# Indikator.net
KiCad netlist of a schematic drawn in Altium Designer
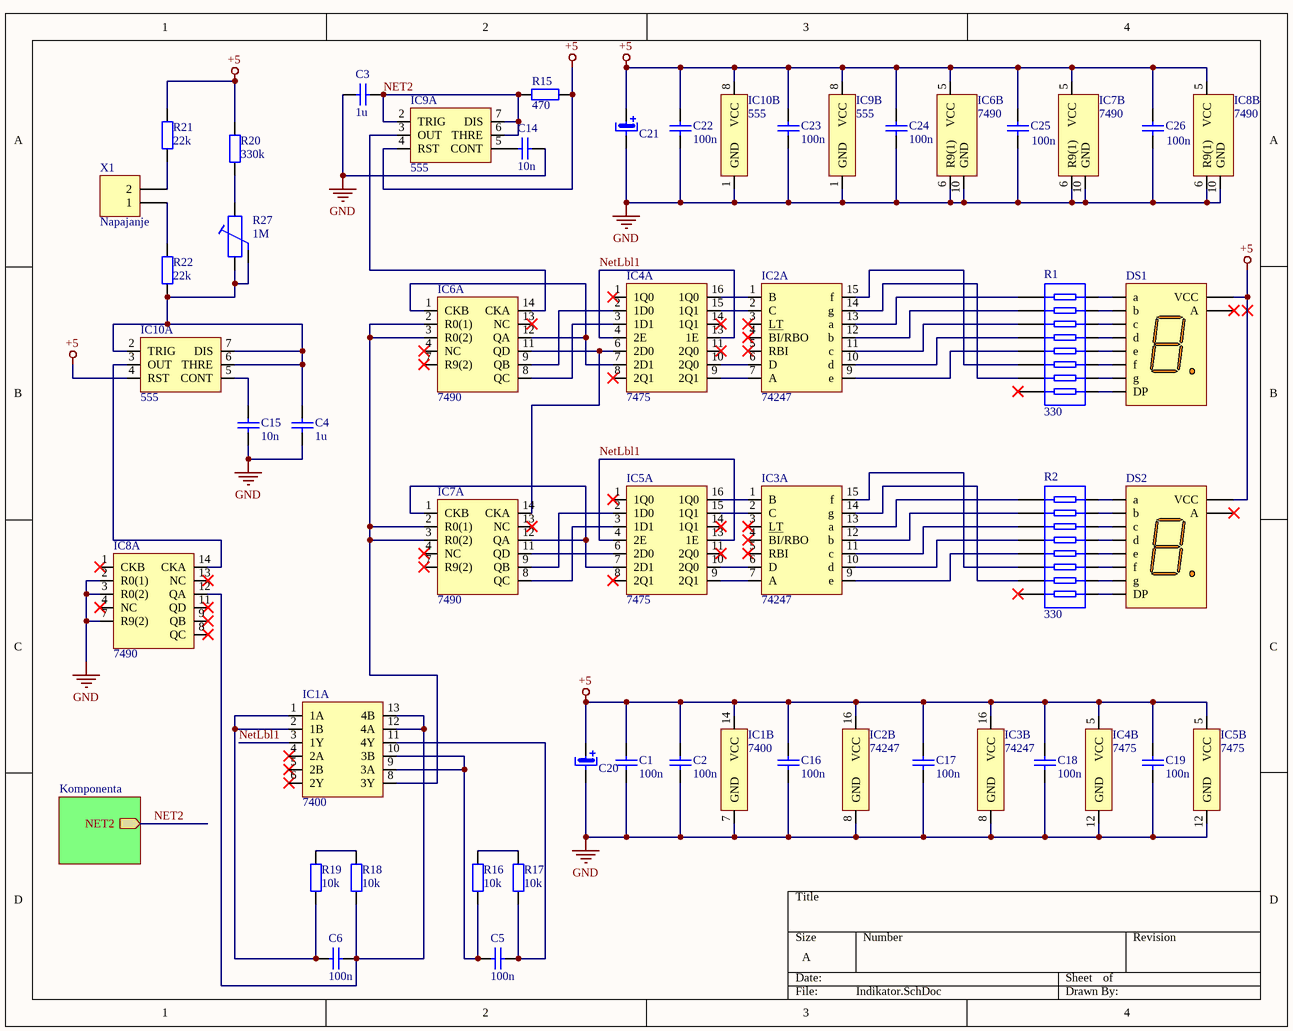
[diagram p0: Indikator.SchDoc]

(export (version "E")
  (design (tool "Eeschema 10.0.6"))
  (components
    (comp (ref "C1")
      (value "100n")
      (footprint "RAD-0.3")
      (description "Capacitor")
      (fields (field (name "PUBLISHER") "Altium Limited"))
      (libsource (lib "Miscellaneous Devices") (part "Cap"))
    )
    (comp (ref "C2")
      (value "100n")
      (footprint "RAD-0.3")
      (description "Capacitor")
      (fields (field (name "PUBLISHER") "Altium Limited"))
      (libsource (lib "Miscellaneous Devices") (part "Cap"))
    )
    (comp (ref "C3")
      (value "1u")
      (footprint "RAD-0.3")
      (description "Capacitor")
      (fields (field (name "PUBLISHER") "Altium Limited"))
      (libsource (lib "Miscellaneous Devices") (part "Cap"))
    )
    (comp (ref "C4")
      (value "1u")
      (footprint "RAD-0.3")
      (description "Capacitor")
      (fields (field (name "PUBLISHER") "Altium Limited"))
      (libsource (lib "Miscellaneous Devices") (part "Cap"))
    )
    (comp (ref "C5")
      (value "100n")
      (footprint "RAD-0.3")
      (description "Capacitor")
      (fields (field (name "PUBLISHER") "Altium Limited"))
      (libsource (lib "Miscellaneous Devices") (part "Cap"))
    )
    (comp (ref "C6")
      (value "100n")
      (footprint "RAD-0.3")
      (description "Capacitor")
      (fields (field (name "PUBLISHER") "Altium Limited"))
      (libsource (lib "Miscellaneous Devices") (part "Cap"))
    )
    (comp (ref "C14")
      (value "10n")
      (footprint "RAD-0.3")
      (description "Capacitor")
      (fields (field (name "PUBLISHER") "Altium Limited"))
      (libsource (lib "Miscellaneous Devices") (part "Cap"))
    )
    (comp (ref "C15")
      (value "10n")
      (footprint "RAD-0.3")
      (description "Capacitor")
      (fields (field (name "PUBLISHER") "Altium Limited"))
      (libsource (lib "Miscellaneous Devices") (part "Cap"))
    )
    (comp (ref "C16")
      (value "100n")
      (footprint "RAD-0.3")
      (description "Capacitor")
      (fields (field (name "PUBLISHER") "Altium Limited"))
      (libsource (lib "Miscellaneous Devices") (part "Cap"))
    )
    (comp (ref "C17")
      (value "100n")
      (footprint "RAD-0.3")
      (description "Capacitor")
      (fields (field (name "PUBLISHER") "Altium Limited"))
      (libsource (lib "Miscellaneous Devices") (part "Cap"))
    )
    (comp (ref "C18")
      (value "100n")
      (footprint "RAD-0.3")
      (description "Capacitor")
      (fields (field (name "PUBLISHER") "Altium Limited"))
      (libsource (lib "Miscellaneous Devices") (part "Cap"))
    )
    (comp (ref "C19")
      (value "100n")
      (footprint "RAD-0.3")
      (description "Capacitor")
      (fields (field (name "PUBLISHER") "Altium Limited"))
      (libsource (lib "Miscellaneous Devices") (part "Cap"))
    )
    (comp (ref "C20") (value "Elko") (footprint "RB7.6-15") (libsource (lib "Indikator_lib") (part "Elko")))
    (comp (ref "C21") (value "Elko") (footprint "RB7.6-15") (libsource (lib "Indikator_lib") (part "Elko")))
    (comp (ref "C22")
      (value "100n")
      (footprint "RAD-0.3")
      (description "Capacitor")
      (fields (field (name "PUBLISHER") "Altium Limited"))
      (libsource (lib "Miscellaneous Devices") (part "Cap"))
    )
    (comp (ref "C23")
      (value "100n")
      (footprint "RAD-0.3")
      (description "Capacitor")
      (fields (field (name "PUBLISHER") "Altium Limited"))
      (libsource (lib "Miscellaneous Devices") (part "Cap"))
    )
    (comp (ref "C24")
      (value "100n")
      (footprint "RAD-0.3")
      (description "Capacitor")
      (fields (field (name "PUBLISHER") "Altium Limited"))
      (libsource (lib "Miscellaneous Devices") (part "Cap"))
    )
    (comp (ref "C25")
      (value "100n")
      (footprint "RAD-0.3")
      (description "Capacitor")
      (fields (field (name "PUBLISHER") "Altium Limited"))
      (libsource (lib "Miscellaneous Devices") (part "Cap"))
    )
    (comp (ref "C26")
      (value "100n")
      (footprint "RAD-0.3")
      (description "Capacitor")
      (fields (field (name "PUBLISHER") "Altium Limited"))
      (libsource (lib "Miscellaneous Devices") (part "Cap"))
    )
    (comp (ref "DS1")
      (value "Dpy Amber-CA")
      (footprint "A")
      (description "7.62 mm Black Surface Orange 7-Segment Display: CA, RH DP")
      (fields (field (name "PUBLISHER") "Altium Limited"))
      (libsource (lib "Miscellaneous Devices") (part "Dpy Amber-CA"))
    )
    (comp (ref "DS2")
      (value "Dpy Amber-CA")
      (footprint "A")
      (description "7.62 mm Black Surface Orange 7-Segment Display: CA, RH DP")
      (fields (field (name "PUBLISHER") "Altium Limited"))
      (libsource (lib "Miscellaneous Devices") (part "Dpy Amber-CA"))
    )
    (comp (ref "IC1") (value "7400") (footprint "DIP-14") (libsource (lib "Indikator_lib") (part "7400")))
    (comp (ref "IC2") (value "74247") (footprint "DIP-16") (libsource (lib "Indikator_lib") (part "74247")))
    (comp (ref "IC3") (value "74247") (footprint "DIP-16") (libsource (lib "Indikator_lib") (part "74247")))
    (comp (ref "IC4") (value "7475") (footprint "DIP-16") (libsource (lib "Indikator_lib") (part "7475")))
    (comp (ref "IC5") (value "7475") (footprint "DIP-16") (libsource (lib "Indikator_lib") (part "7475")))
    (comp (ref "IC6") (value "7490") (footprint "DIP-14") (libsource (lib "Indikator_lib") (part "7490")))
    (comp (ref "IC7") (value "7490") (footprint "DIP-14") (libsource (lib "Indikator_lib") (part "7490")))
    (comp (ref "IC8") (value "7490") (footprint "DIP-14") (libsource (lib "Indikator_lib") (part "7490")))
    (comp (ref "IC9") (value "555") (footprint "DIP-8") (libsource (lib "Indikator_lib") (part "555")))
    (comp (ref "IC10") (value "555") (footprint "DIP-8") (libsource (lib "Indikator_lib") (part "555")))
    (comp (ref "R1")
      (value "330")
      (footprint "SSOP16_N")
      (description "Isolated Resistor Network")
      (fields (field (name "PUBLISHER") "Altium Limited"))
      (libsource (lib "Miscellaneous Devices") (part "Res Pack4"))
    )
    (comp (ref "R2")
      (value "330")
      (footprint "SSOP16_N")
      (description "Isolated Resistor Network")
      (fields (field (name "PUBLISHER") "Altium Limited"))
      (libsource (lib "Miscellaneous Devices") (part "Res Pack4"))
    )
    (comp (ref "R15")
      (value "470")
      (footprint "AXIAL-0.4")
      (description "Resistor")
      (fields (field (name "PUBLISHER") "Altium Limited"))
      (libsource (lib "") (part "Res2_2"))
    )
    (comp (ref "R16")
      (value "10k")
      (footprint "AXIAL-0.4")
      (description "Resistor")
      (fields (field (name "PUBLISHER") "Altium Limited"))
      (libsource (lib "") (part "Res2_1"))
    )
    (comp (ref "R17")
      (value "10k")
      (footprint "AXIAL-0.4")
      (description "Resistor")
      (fields (field (name "PUBLISHER") "Altium Limited"))
      (libsource (lib "") (part "Res2_1"))
    )
    (comp (ref "R18")
      (value "10k")
      (footprint "AXIAL-0.4")
      (description "Resistor")
      (fields (field (name "PUBLISHER") "Altium Limited"))
      (libsource (lib "") (part "Res2_1"))
    )
    (comp (ref "R19")
      (value "10k")
      (footprint "AXIAL-0.4")
      (description "Resistor")
      (fields (field (name "PUBLISHER") "Altium Limited"))
      (libsource (lib "") (part "Res2_1"))
    )
    (comp (ref "R20")
      (value "330k")
      (footprint "AXIAL-0.4")
      (description "Resistor")
      (fields (field (name "PUBLISHER") "Altium Limited"))
      (libsource (lib "") (part "Res2_1"))
    )
    (comp (ref "R21")
      (value "22k")
      (footprint "AXIAL-0.4")
      (description "Resistor")
      (fields (field (name "PUBLISHER") "Altium Limited"))
      (libsource (lib "") (part "Res2_1"))
    )
    (comp (ref "R22")
      (value "22k")
      (footprint "AXIAL-0.4")
      (description "Resistor")
      (fields (field (name "PUBLISHER") "Altium Limited"))
      (libsource (lib "Miscellaneous Devices") (part "Res2"))
    )
    (comp (ref "R27") (value "1M") (footprint "14-1210") (libsource (lib "Indikator_lib") (part "Trimmer")))
    (comp (ref "X1")
      (value "Napajanje")
      (footprint "HDR1X2")
      (description "Header, 2-Pin")
      (fields (field (name "PUBLISHER") "Altium Limited"))
      (libsource (lib "Miscellaneous Connectors") (part "Header 2"))
    )
  )
  (nets
    (net (code "1") (name "+5") (class "Default")
      (node (ref "C1") (pin "2") (pinfunction "2_2") (pintype "passive"))
      (node (ref "C16") (pin "2") (pinfunction "2_2") (pintype "passive"))
      (node (ref "C17") (pin "2") (pinfunction "2_2") (pintype "passive"))
      (node (ref "C18") (pin "2") (pinfunction "2_2") (pintype "passive"))
      (node (ref "C19") (pin "2") (pinfunction "2_2") (pintype "passive"))
      (node (ref "C2") (pin "2") (pinfunction "2_2") (pintype "passive"))
      (node (ref "C20") (pin "1") (pinfunction "16_1") (pintype "passive"))
      (node (ref "C21") (pin "1") (pinfunction "16_1") (pintype "passive"))
      (node (ref "C22") (pin "2") (pinfunction "2_2") (pintype "passive"))
      (node (ref "C23") (pin "2") (pinfunction "2_2") (pintype "passive"))
      (node (ref "C24") (pin "2") (pinfunction "2_2") (pintype "passive"))
      (node (ref "C25") (pin "2") (pinfunction "2_2") (pintype "passive"))
      (node (ref "C26") (pin "2") (pinfunction "2_2") (pintype "passive"))
      (node (ref "DS1") (pin "1") (pinfunction "VCC_1") (pintype "passive"))
      (node (ref "DS2") (pin "1") (pinfunction "VCC_1") (pintype "passive"))
      (node (ref "IC1") (pin "14") (pinfunction "VCC_14") (pintype "passive"))
      (node (ref "IC10") (pin "4") (pinfunction "RST_4") (pintype "passive"))
      (node (ref "IC10") (pin "8") (pinfunction "VCC_8") (pintype "passive"))
      (node (ref "IC2") (pin "16") (pinfunction "VCC_16") (pintype "passive"))
      (node (ref "IC3") (pin "16") (pinfunction "VCC_16") (pintype "passive"))
      (node (ref "IC4") (pin "5") (pinfunction "VCC_5") (pintype "passive"))
      (node (ref "IC5") (pin "5") (pinfunction "VCC_5") (pintype "passive"))
      (node (ref "IC6") (pin "5") (pinfunction "VCC_5") (pintype "passive"))
      (node (ref "IC7") (pin "5") (pinfunction "VCC_5") (pintype "passive"))
      (node (ref "IC8") (pin "5") (pinfunction "VCC_5") (pintype "passive"))
      (node (ref "IC9") (pin "4") (pinfunction "RST_4") (pintype "passive"))
      (node (ref "IC9") (pin "8") (pinfunction "VCC_8") (pintype "passive"))
      (node (ref "R15") (pin "2") (pinfunction "2_2") (pintype "passive"))
      (node (ref "R20") (pin "2") (pinfunction "2_2") (pintype "passive"))
      (node (ref "R21") (pin "2") (pinfunction "2_2") (pintype "passive"))
    )
    (net (code "2") (name "/NET2") (class "Default")
      (node (ref "C3") (pin "2") (pinfunction "2_2") (pintype "passive"))
      (node (ref "IC9") (pin "2") (pinfunction "TRIG_2") (pintype "passive"))
      (node (ref "IC9") (pin "6") (pinfunction "THRE_6") (pintype "passive"))
      (node (ref "IC9") (pin "7") (pinfunction "DIS_7") (pintype "passive"))
      (node (ref "R15") (pin "1") (pinfunction "1_1") (pintype "passive"))
    )
    (net (code "3") (name "/NetLbl1") (class "Default")
      (node (ref "IC1") (pin "3") (pinfunction "1Y_3") (pintype "passive"))
      (node (ref "IC4") (pin "13") (pinfunction "1E_13") (pintype "passive"))
      (node (ref "IC4") (pin "4") (pinfunction "2E_4") (pintype "passive"))
      (node (ref "IC5") (pin "13") (pinfunction "1E_13") (pintype "passive"))
      (node (ref "IC5") (pin "4") (pinfunction "2E_4") (pintype "passive"))
    )
    (net (code "4") (name "GND") (class "Default")
      (node (ref "C1") (pin "1") (pinfunction "1_1") (pintype "passive"))
      (node (ref "C14") (pin "2") (pinfunction "2_2") (pintype "passive"))
      (node (ref "C15") (pin "1") (pinfunction "1_1") (pintype "passive"))
      (node (ref "C16") (pin "1") (pinfunction "1_1") (pintype "passive"))
      (node (ref "C17") (pin "1") (pinfunction "1_1") (pintype "passive"))
      (node (ref "C18") (pin "1") (pinfunction "1_1") (pintype "passive"))
      (node (ref "C19") (pin "1") (pinfunction "1_1") (pintype "passive"))
      (node (ref "C2") (pin "1") (pinfunction "1_1") (pintype "passive"))
      (node (ref "C20") (pin "2") (pintype "passive"))
      (node (ref "C21") (pin "2") (pintype "passive"))
      (node (ref "C22") (pin "1") (pinfunction "1_1") (pintype "passive"))
      (node (ref "C23") (pin "1") (pinfunction "1_1") (pintype "passive"))
      (node (ref "C24") (pin "1") (pinfunction "1_1") (pintype "passive"))
      (node (ref "C25") (pin "1") (pinfunction "1_1") (pintype "passive"))
      (node (ref "C26") (pin "1") (pinfunction "1_1") (pintype "passive"))
      (node (ref "C3") (pin "1") (pinfunction "1_1") (pintype "passive"))
      (node (ref "C4") (pin "2") (pinfunction "2_2") (pintype "passive"))
      (node (ref "IC1") (pin "7") (pinfunction "GND_7") (pintype "passive"))
      (node (ref "IC10") (pin "1") (pinfunction "GND_1") (pintype "passive"))
      (node (ref "IC2") (pin "8") (pinfunction "GND_8") (pintype "passive"))
      (node (ref "IC3") (pin "8") (pinfunction "GND_8") (pintype "passive"))
      (node (ref "IC4") (pin "12") (pinfunction "GND_12") (pintype "passive"))
      (node (ref "IC5") (pin "12") (pinfunction "GND_12") (pintype "passive"))
      (node (ref "IC6") (pin "10") (pinfunction "GND_10") (pintype "passive"))
      (node (ref "IC6") (pin "6") (pinfunction "R9(1)_6") (pintype "passive"))
      (node (ref "IC7") (pin "10") (pinfunction "GND_10") (pintype "passive"))
      (node (ref "IC7") (pin "6") (pinfunction "R9(1)_6") (pintype "passive"))
      (node (ref "IC8") (pin "10") (pinfunction "GND_10") (pintype "passive"))
      (node (ref "IC8") (pin "2") (pinfunction "R0(1)_2") (pintype "passive"))
      (node (ref "IC8") (pin "3") (pinfunction "R0(2)_3") (pintype "passive"))
      (node (ref "IC8") (pin "6") (pinfunction "R9(1)_6") (pintype "passive"))
      (node (ref "IC8") (pin "7") (pinfunction "R9(2)_7") (pintype "passive"))
      (node (ref "IC9") (pin "1") (pinfunction "GND_1") (pintype "passive"))
    )
    (net (code "5") (name "Net-(DS1-DP)") (class "Default")
      (node (ref "DS1") (pin "7") (pinfunction "DP_7") (pintype "passive"))
      (node (ref "R1") (pin "9") (pinfunction "9_9") (pintype "passive"))
    )
    (net (code "6") (name "Net-(DS1-a)") (class "Default")
      (node (ref "DS1") (pin "10") (pinfunction "a_10") (pintype "passive"))
      (node (ref "R1") (pin "16") (pinfunction "16_16") (pintype "passive"))
    )
    (net (code "7") (name "Net-(DS1-b)") (class "Default")
      (node (ref "DS1") (pin "9") (pinfunction "b_9") (pintype "passive"))
      (node (ref "R1") (pin "15") (pinfunction "15_15") (pintype "passive"))
    )
    (net (code "8") (name "Net-(DS1-c)") (class "Default")
      (node (ref "DS1") (pin "8") (pinfunction "c_8") (pintype "passive"))
      (node (ref "R1") (pin "14") (pinfunction "14_14") (pintype "passive"))
    )
    (net (code "9") (name "Net-(DS1-d)") (class "Default")
      (node (ref "DS1") (pin "5") (pinfunction "d_5") (pintype "passive"))
      (node (ref "R1") (pin "13") (pinfunction "13_13") (pintype "passive"))
    )
    (net (code "10") (name "Net-(DS1-e)") (class "Default")
      (node (ref "DS1") (pin "4") (pinfunction "e_4") (pintype "passive"))
      (node (ref "R1") (pin "12") (pinfunction "12_12") (pintype "passive"))
    )
    (net (code "11") (name "Net-(DS1-f)") (class "Default")
      (node (ref "DS1") (pin "2") (pinfunction "f_2") (pintype "passive"))
      (node (ref "R1") (pin "11") (pinfunction "11_11") (pintype "passive"))
    )
    (net (code "12") (name "Net-(DS1-g)") (class "Default")
      (node (ref "DS1") (pin "3") (pinfunction "g_3") (pintype "passive"))
      (node (ref "R1") (pin "10") (pinfunction "10_10") (pintype "passive"))
    )
    (net (code "13") (name "Net-(DS2-DP)") (class "Default")
      (node (ref "DS2") (pin "7") (pinfunction "DP_7") (pintype "passive"))
      (node (ref "R2") (pin "9") (pinfunction "9_9") (pintype "passive"))
    )
    (net (code "14") (name "Net-(DS2-a)") (class "Default")
      (node (ref "DS2") (pin "10") (pinfunction "a_10") (pintype "passive"))
      (node (ref "R2") (pin "16") (pinfunction "16_16") (pintype "passive"))
    )
    (net (code "15") (name "Net-(DS2-b)") (class "Default")
      (node (ref "DS2") (pin "9") (pinfunction "b_9") (pintype "passive"))
      (node (ref "R2") (pin "15") (pinfunction "15_15") (pintype "passive"))
    )
    (net (code "16") (name "Net-(DS2-c)") (class "Default")
      (node (ref "DS2") (pin "8") (pinfunction "c_8") (pintype "passive"))
      (node (ref "R2") (pin "14") (pinfunction "14_14") (pintype "passive"))
    )
    (net (code "17") (name "Net-(DS2-d)") (class "Default")
      (node (ref "DS2") (pin "5") (pinfunction "d_5") (pintype "passive"))
      (node (ref "R2") (pin "13") (pinfunction "13_13") (pintype "passive"))
    )
    (net (code "18") (name "Net-(DS2-e)") (class "Default")
      (node (ref "DS2") (pin "4") (pinfunction "e_4") (pintype "passive"))
      (node (ref "R2") (pin "12") (pinfunction "12_12") (pintype "passive"))
    )
    (net (code "19") (name "Net-(DS2-f)") (class "Default")
      (node (ref "DS2") (pin "2") (pinfunction "f_2") (pintype "passive"))
      (node (ref "R2") (pin "11") (pinfunction "11_11") (pintype "passive"))
    )
    (net (code "20") (name "Net-(DS2-g)") (class "Default")
      (node (ref "DS2") (pin "3") (pinfunction "g_3") (pintype "passive"))
      (node (ref "R2") (pin "10") (pinfunction "10_10") (pintype "passive"))
    )
    (net (code "21") (name "Net-(IC1A-1A)") (class "Default")
      (node (ref "C6") (pin "2") (pinfunction "2_2") (pintype "passive"))
      (node (ref "IC1") (pin "1") (pinfunction "1A_1") (pintype "passive"))
      (node (ref "IC1") (pin "2") (pinfunction "1B_2") (pintype "passive"))
      (node (ref "R19") (pin "1") (pinfunction "1_1") (pintype "passive"))
    )
    (net (code "22") (name "Net-(IC1A-3A)") (class "Default")
      (node (ref "C5") (pin "2") (pinfunction "2_2") (pintype "passive"))
      (node (ref "IC1") (pin "10") (pinfunction "3B_10") (pintype "passive"))
      (node (ref "IC1") (pin "9") (pinfunction "3A_9") (pintype "passive"))
      (node (ref "R16") (pin "1") (pinfunction "1_1") (pintype "passive"))
    )
    (net (code "23") (name "Net-(IC1A-3Y)") (class "Default")
      (node (ref "IC1") (pin "8") (pinfunction "3Y_8") (pintype "passive"))
      (node (ref "IC6") (pin "2") (pinfunction "R0(1)_2") (pintype "passive"))
      (node (ref "IC6") (pin "3") (pinfunction "R0(2)_3") (pintype "passive"))
      (node (ref "IC7") (pin "2") (pinfunction "R0(1)_2") (pintype "passive"))
      (node (ref "IC7") (pin "3") (pinfunction "R0(2)_3") (pintype "passive"))
    )
    (net (code "24") (name "Net-(IC1A-4A)") (class "Default")
      (node (ref "C6") (pin "1") (pinfunction "1_1") (pintype "passive"))
      (node (ref "IC1") (pin "12") (pinfunction "4A_12") (pintype "passive"))
      (node (ref "IC1") (pin "13") (pinfunction "4B_13") (pintype "passive"))
      (node (ref "IC8") (pin "12") (pinfunction "QA_12") (pintype "passive"))
      (node (ref "R18") (pin "1") (pinfunction "1_1") (pintype "passive"))
    )
    (net (code "25") (name "Net-(IC1A-4Y)") (class "Default")
      (node (ref "C5") (pin "1") (pinfunction "1_1") (pintype "passive"))
      (node (ref "IC1") (pin "11") (pinfunction "4Y_11") (pintype "passive"))
      (node (ref "R17") (pin "1") (pinfunction "1_1") (pintype "passive"))
    )
    (net (code "26") (name "Net-(IC2A-A)") (class "Default")
      (node (ref "IC2") (pin "7") (pinfunction "A_7") (pintype "passive"))
      (node (ref "IC4") (pin "9") (pinfunction "2Q1_9") (pintype "passive"))
    )
    (net (code "27") (name "Net-(IC2A-B)") (class "Default")
      (node (ref "IC2") (pin "1") (pinfunction "B_1") (pintype "passive"))
      (node (ref "IC4") (pin "16") (pinfunction "1Q0_16") (pintype "passive"))
    )
    (net (code "28") (name "Net-(IC2A-C)") (class "Default")
      (node (ref "IC2") (pin "2") (pinfunction "C_2") (pintype "passive"))
      (node (ref "IC4") (pin "15") (pinfunction "1Q1_15") (pintype "passive"))
    )
    (net (code "29") (name "Net-(IC2A-D)") (class "Default")
      (node (ref "IC2") (pin "6") (pinfunction "D_6") (pintype "passive"))
      (node (ref "IC4") (pin "10") (pinfunction "2Q0_10") (pintype "passive"))
    )
    (net (code "30") (name "Net-(IC2A-a)") (class "Default")
      (node (ref "IC2") (pin "13") (pinfunction "a_13") (pintype "passive"))
      (node (ref "R1") (pin "1") (pinfunction "1_1") (pintype "passive"))
    )
    (net (code "31") (name "Net-(IC2A-b)") (class "Default")
      (node (ref "IC2") (pin "12") (pinfunction "b_12") (pintype "passive"))
      (node (ref "R1") (pin "2") (pinfunction "2_2") (pintype "passive"))
    )
    (net (code "32") (name "Net-(IC2A-c)") (class "Default")
      (node (ref "IC2") (pin "11") (pinfunction "c_11") (pintype "passive"))
      (node (ref "R1") (pin "3") (pinfunction "3_3") (pintype "passive"))
    )
    (net (code "33") (name "Net-(IC2A-d)") (class "Default")
      (node (ref "IC2") (pin "10") (pinfunction "d_10") (pintype "passive"))
      (node (ref "R1") (pin "4") (pinfunction "4_4") (pintype "passive"))
    )
    (net (code "34") (name "Net-(IC2A-e)") (class "Default")
      (node (ref "IC2") (pin "9") (pinfunction "e_9") (pintype "passive"))
      (node (ref "R1") (pin "5") (pinfunction "5_5") (pintype "passive"))
    )
    (net (code "35") (name "Net-(IC2A-f)") (class "Default")
      (node (ref "IC2") (pin "15") (pinfunction "f_15") (pintype "passive"))
      (node (ref "R1") (pin "6") (pinfunction "6_6") (pintype "passive"))
    )
    (net (code "36") (name "Net-(IC2A-g)") (class "Default")
      (node (ref "IC2") (pin "14") (pinfunction "g_14") (pintype "passive"))
      (node (ref "R1") (pin "7") (pinfunction "7_7") (pintype "passive"))
    )
    (net (code "37") (name "Net-(IC3A-A)") (class "Default")
      (node (ref "IC3") (pin "7") (pinfunction "A_7") (pintype "passive"))
      (node (ref "IC5") (pin "9") (pinfunction "2Q1_9") (pintype "passive"))
    )
    (net (code "38") (name "Net-(IC3A-B)") (class "Default")
      (node (ref "IC3") (pin "1") (pinfunction "B_1") (pintype "passive"))
      (node (ref "IC5") (pin "16") (pinfunction "1Q0_16") (pintype "passive"))
    )
    (net (code "39") (name "Net-(IC3A-C)") (class "Default")
      (node (ref "IC3") (pin "2") (pinfunction "C_2") (pintype "passive"))
      (node (ref "IC5") (pin "15") (pinfunction "1Q1_15") (pintype "passive"))
    )
    (net (code "40") (name "Net-(IC3A-D)") (class "Default")
      (node (ref "IC3") (pin "6") (pinfunction "D_6") (pintype "passive"))
      (node (ref "IC5") (pin "10") (pinfunction "2Q0_10") (pintype "passive"))
    )
    (net (code "41") (name "Net-(IC3A-a)") (class "Default")
      (node (ref "IC3") (pin "13") (pinfunction "a_13") (pintype "passive"))
      (node (ref "R2") (pin "1") (pinfunction "1_1") (pintype "passive"))
    )
    (net (code "42") (name "Net-(IC3A-b)") (class "Default")
      (node (ref "IC3") (pin "12") (pinfunction "b_12") (pintype "passive"))
      (node (ref "R2") (pin "2") (pinfunction "2_2") (pintype "passive"))
    )
    (net (code "43") (name "Net-(IC3A-c)") (class "Default")
      (node (ref "IC3") (pin "11") (pinfunction "c_11") (pintype "passive"))
      (node (ref "R2") (pin "3") (pinfunction "3_3") (pintype "passive"))
    )
    (net (code "44") (name "Net-(IC3A-d)") (class "Default")
      (node (ref "IC3") (pin "10") (pinfunction "d_10") (pintype "passive"))
      (node (ref "R2") (pin "4") (pinfunction "4_4") (pintype "passive"))
    )
    (net (code "45") (name "Net-(IC3A-e)") (class "Default")
      (node (ref "IC3") (pin "9") (pinfunction "e_9") (pintype "passive"))
      (node (ref "R2") (pin "5") (pinfunction "5_5") (pintype "passive"))
    )
    (net (code "46") (name "Net-(IC3A-f)") (class "Default")
      (node (ref "IC3") (pin "15") (pinfunction "f_15") (pintype "passive"))
      (node (ref "R2") (pin "6") (pinfunction "6_6") (pintype "passive"))
    )
    (net (code "47") (name "Net-(IC3A-g)") (class "Default")
      (node (ref "IC3") (pin "14") (pinfunction "g_14") (pintype "passive"))
      (node (ref "R2") (pin "7") (pinfunction "7_7") (pintype "passive"))
    )
    (net (code "48") (name "Net-(IC4A-1D0)") (class "Default")
      (node (ref "IC4") (pin "2") (pinfunction "1D0_2") (pintype "passive"))
      (node (ref "IC6") (pin "9") (pinfunction "QB_9") (pintype "passive"))
    )
    (net (code "49") (name "Net-(IC4A-1D1)") (class "Default")
      (node (ref "IC4") (pin "3") (pinfunction "1D1_3") (pintype "passive"))
      (node (ref "IC6") (pin "8") (pinfunction "QC_8") (pintype "passive"))
    )
    (net (code "50") (name "Net-(IC4A-2D0)") (class "Default")
      (node (ref "IC4") (pin "6") (pinfunction "2D0_6") (pintype "passive"))
      (node (ref "IC6") (pin "11") (pinfunction "QD_11") (pintype "passive"))
      (node (ref "IC7") (pin "14") (pinfunction "CKA_14") (pintype "passive"))
    )
    (net (code "51") (name "Net-(IC4A-2D1)") (class "Default")
      (node (ref "IC4") (pin "7") (pinfunction "2D1_7") (pintype "passive"))
      (node (ref "IC6") (pin "1") (pinfunction "CKB_1") (pintype "passive"))
      (node (ref "IC6") (pin "12") (pinfunction "QA_12") (pintype "passive"))
    )
    (net (code "52") (name "Net-(IC5A-1D0)") (class "Default")
      (node (ref "IC5") (pin "2") (pinfunction "1D0_2") (pintype "passive"))
      (node (ref "IC7") (pin "9") (pinfunction "QB_9") (pintype "passive"))
    )
    (net (code "53") (name "Net-(IC5A-1D1)") (class "Default")
      (node (ref "IC5") (pin "3") (pinfunction "1D1_3") (pintype "passive"))
      (node (ref "IC7") (pin "8") (pinfunction "QC_8") (pintype "passive"))
    )
    (net (code "54") (name "Net-(IC5A-2D0)") (class "Default")
      (node (ref "IC5") (pin "6") (pinfunction "2D0_6") (pintype "passive"))
      (node (ref "IC7") (pin "11") (pinfunction "QD_11") (pintype "passive"))
    )
    (net (code "55") (name "Net-(IC5A-2D1)") (class "Default")
      (node (ref "IC5") (pin "7") (pinfunction "2D1_7") (pintype "passive"))
      (node (ref "IC7") (pin "1") (pinfunction "CKB_1") (pintype "passive"))
      (node (ref "IC7") (pin "12") (pinfunction "QA_12") (pintype "passive"))
    )
    (net (code "56") (name "Net-(IC6A-CKA)") (class "Default")
      (node (ref "IC6") (pin "14") (pinfunction "CKA_14") (pintype "passive"))
      (node (ref "IC9") (pin "3") (pinfunction "OUT_3") (pintype "passive"))
    )
    (net (code "57") (name "Net-(IC9A-CONT)") (class "Default")
      (node (ref "C14") (pin "1") (pinfunction "1_1") (pintype "passive"))
      (node (ref "IC9") (pin "5") (pinfunction "CONT_5") (pintype "passive"))
    )
    (net (code "58") (name "Net-(IC10A-CONT)") (class "Default")
      (node (ref "C15") (pin "2") (pinfunction "2_2") (pintype "passive"))
      (node (ref "IC10") (pin "5") (pinfunction "CONT_5") (pintype "passive"))
    )
    (net (code "59") (name "Net-(IC10A-DIS)") (class "Default")
      (node (ref "C4") (pin "1") (pinfunction "1_1") (pintype "passive"))
      (node (ref "IC10") (pin "2") (pinfunction "TRIG_2") (pintype "passive"))
      (node (ref "IC10") (pin "6") (pinfunction "THRE_6") (pintype "passive"))
      (node (ref "IC10") (pin "7") (pinfunction "DIS_7") (pintype "passive"))
      (node (ref "R22") (pin "2") (pinfunction "2_2") (pintype "passive"))
      (node (ref "R27") (pin "1") (pinfunction "1_1") (pintype "passive"))
      (node (ref "R27") (pin "2") (pinfunction "2_2") (pintype "passive"))
    )
    (net (code "60") (name "Net-(IC10A-OUT)") (class "Default")
      (node (ref "IC10") (pin "3") (pinfunction "OUT_3") (pintype "passive"))
      (node (ref "IC8") (pin "14") (pinfunction "CKA_14") (pintype "passive"))
    )
    (net (code "61") (name "Net-(R16-Pad2)") (class "Default")
      (node (ref "R16") (pin "2") (pinfunction "2_2") (pintype "passive"))
      (node (ref "R17") (pin "2") (pinfunction "2_2") (pintype "passive"))
    )
    (net (code "62") (name "Net-(R18-Pad2)") (class "Default")
      (node (ref "R18") (pin "2") (pinfunction "2_2") (pintype "passive"))
      (node (ref "R19") (pin "2") (pinfunction "2_2") (pintype "passive"))
    )
    (net (code "63") (name "Net-(R20-Pad1)") (class "Default")
      (node (ref "R20") (pin "1") (pinfunction "1_1") (pintype "passive"))
      (node (ref "R27") (pin "0") (pinfunction "0_0") (pintype "passive"))
    )
    (net (code "64") (name "Net-(R21-Pad1)") (class "Default")
      (node (ref "R21") (pin "1") (pinfunction "1_1") (pintype "passive"))
      (node (ref "X1") (pin "2") (pinfunction "2_2") (pintype "passive"))
    )
    (net (code "65") (name "Net-(R22-Pad1)") (class "Default")
      (node (ref "R22") (pin "1") (pinfunction "1_1") (pintype "passive"))
      (node (ref "X1") (pin "1") (pinfunction "1_1") (pintype "passive"))
    )
    (net (code "66") (name "unconnected-(DS1-A-Pad6)") (class "Default")
      (node (ref "DS1") (pin "6") (pinfunction "A_6") (pintype "passive+no_connect"))
    )
    (net (code "67") (name "unconnected-(DS2-A-Pad6)") (class "Default")
      (node (ref "DS2") (pin "6") (pinfunction "A_6") (pintype "passive+no_connect"))
    )
    (net (code "68") (name "unconnected-(IC1A-2A-Pad4)") (class "Default")
      (node (ref "IC1") (pin "4") (pinfunction "2A_4") (pintype "passive+no_connect"))
    )
    (net (code "69") (name "unconnected-(IC1A-2B-Pad5)") (class "Default")
      (node (ref "IC1") (pin "5") (pinfunction "2B_5") (pintype "passive+no_connect"))
    )
    (net (code "70") (name "unconnected-(IC1A-2Y-Pad6)") (class "Default")
      (node (ref "IC1") (pin "6") (pinfunction "2Y_6") (pintype "passive+no_connect"))
    )
    (net (code "71") (name "unconnected-(IC2A-BI{slash}RBO-Pad4)") (class "Default")
      (node (ref "IC2") (pin "4") (pinfunction "BI/RBO_4") (pintype "passive+no_connect"))
    )
    (net (code "72") (name "unconnected-(IC2A-LT-Pad3)") (class "Default")
      (node (ref "IC2") (pin "3") (pinfunction "LT_3") (pintype "passive+no_connect"))
    )
    (net (code "73") (name "unconnected-(IC2A-RBI-Pad5)") (class "Default")
      (node (ref "IC2") (pin "5") (pinfunction "RBI_5") (pintype "passive+no_connect"))
    )
    (net (code "74") (name "unconnected-(IC3A-BI{slash}RBO-Pad4)") (class "Default")
      (node (ref "IC3") (pin "4") (pinfunction "BI/RBO_4") (pintype "passive+no_connect"))
    )
    (net (code "75") (name "unconnected-(IC3A-LT-Pad3)") (class "Default")
      (node (ref "IC3") (pin "3") (pinfunction "LT_3") (pintype "passive+no_connect"))
    )
    (net (code "76") (name "unconnected-(IC3A-RBI-Pad5)") (class "Default")
      (node (ref "IC3") (pin "5") (pinfunction "RBI_5") (pintype "passive+no_connect"))
    )
    (net (code "77") (name "unconnected-(IC4A-1Q0-Pad1)") (class "Default")
      (node (ref "IC4") (pin "1") (pinfunction "1Q0_1") (pintype "passive+no_connect"))
    )
    (net (code "78") (name "unconnected-(IC4A-1Q1-Pad14)") (class "Default")
      (node (ref "IC4") (pin "14") (pinfunction "1Q1_14") (pintype "passive+no_connect"))
    )
    (net (code "79") (name "unconnected-(IC4A-2Q0-Pad11)") (class "Default")
      (node (ref "IC4") (pin "11") (pinfunction "2Q0_11") (pintype "passive+no_connect"))
    )
    (net (code "80") (name "unconnected-(IC4A-2Q1-Pad8)") (class "Default")
      (node (ref "IC4") (pin "8") (pinfunction "2Q1_8") (pintype "passive+no_connect"))
    )
    (net (code "81") (name "unconnected-(IC5A-1Q0-Pad1)") (class "Default")
      (node (ref "IC5") (pin "1") (pinfunction "1Q0_1") (pintype "passive+no_connect"))
    )
    (net (code "82") (name "unconnected-(IC5A-1Q1-Pad14)") (class "Default")
      (node (ref "IC5") (pin "14") (pinfunction "1Q1_14") (pintype "passive+no_connect"))
    )
    (net (code "83") (name "unconnected-(IC5A-2Q0-Pad11)") (class "Default")
      (node (ref "IC5") (pin "11") (pinfunction "2Q0_11") (pintype "passive+no_connect"))
    )
    (net (code "84") (name "unconnected-(IC5A-2Q1-Pad8)") (class "Default")
      (node (ref "IC5") (pin "8") (pinfunction "2Q1_8") (pintype "passive+no_connect"))
    )
    (net (code "85") (name "unconnected-(IC6A-NC-Pad4)") (class "Default")
      (node (ref "IC6") (pin "4") (pinfunction "NC_4") (pintype "passive+no_connect"))
    )
    (net (code "86") (name "unconnected-(IC6A-NC-Pad13)") (class "Default")
      (node (ref "IC6") (pin "13") (pinfunction "NC_13") (pintype "passive+no_connect"))
    )
    (net (code "87") (name "unconnected-(IC6A-R9(2)-Pad7)") (class "Default")
      (node (ref "IC6") (pin "7") (pinfunction "R9(2)_7") (pintype "passive+no_connect"))
    )
    (net (code "88") (name "unconnected-(IC7A-NC-Pad4)") (class "Default")
      (node (ref "IC7") (pin "4") (pinfunction "NC_4") (pintype "passive+no_connect"))
    )
    (net (code "89") (name "unconnected-(IC7A-NC-Pad13)") (class "Default")
      (node (ref "IC7") (pin "13") (pinfunction "NC_13") (pintype "passive+no_connect"))
    )
    (net (code "90") (name "unconnected-(IC7A-R9(2)-Pad7)") (class "Default")
      (node (ref "IC7") (pin "7") (pinfunction "R9(2)_7") (pintype "passive+no_connect"))
    )
    (net (code "91") (name "unconnected-(IC8A-CKB-Pad1)") (class "Default")
      (node (ref "IC8") (pin "1") (pinfunction "CKB_1") (pintype "passive+no_connect"))
    )
    (net (code "92") (name "unconnected-(IC8A-NC-Pad4)") (class "Default")
      (node (ref "IC8") (pin "4") (pinfunction "NC_4") (pintype "passive+no_connect"))
    )
    (net (code "93") (name "unconnected-(IC8A-NC-Pad13)") (class "Default")
      (node (ref "IC8") (pin "13") (pinfunction "NC_13") (pintype "passive+no_connect"))
    )
    (net (code "94") (name "unconnected-(IC8A-QB-Pad9)") (class "Default")
      (node (ref "IC8") (pin "9") (pinfunction "QB_9") (pintype "passive+no_connect"))
    )
    (net (code "95") (name "unconnected-(IC8A-QC-Pad8)") (class "Default")
      (node (ref "IC8") (pin "8") (pinfunction "QC_8") (pintype "passive+no_connect"))
    )
    (net (code "96") (name "unconnected-(IC8A-QD-Pad11)") (class "Default")
      (node (ref "IC8") (pin "11") (pinfunction "QD_11") (pintype "passive+no_connect"))
    )
    (net (code "97") (name "unconnected-(R1-Pad8)") (class "Default")
      (node (ref "R1") (pin "8") (pinfunction "8_8") (pintype "passive+no_connect"))
    )
    (net (code "98") (name "unconnected-(R2-Pad8)") (class "Default")
      (node (ref "R2") (pin "8") (pinfunction "8_8") (pintype "passive+no_connect"))
    )
  )
)
